# Sheet1.net
KiCad netlist of a schematic drawn in Altium Designer
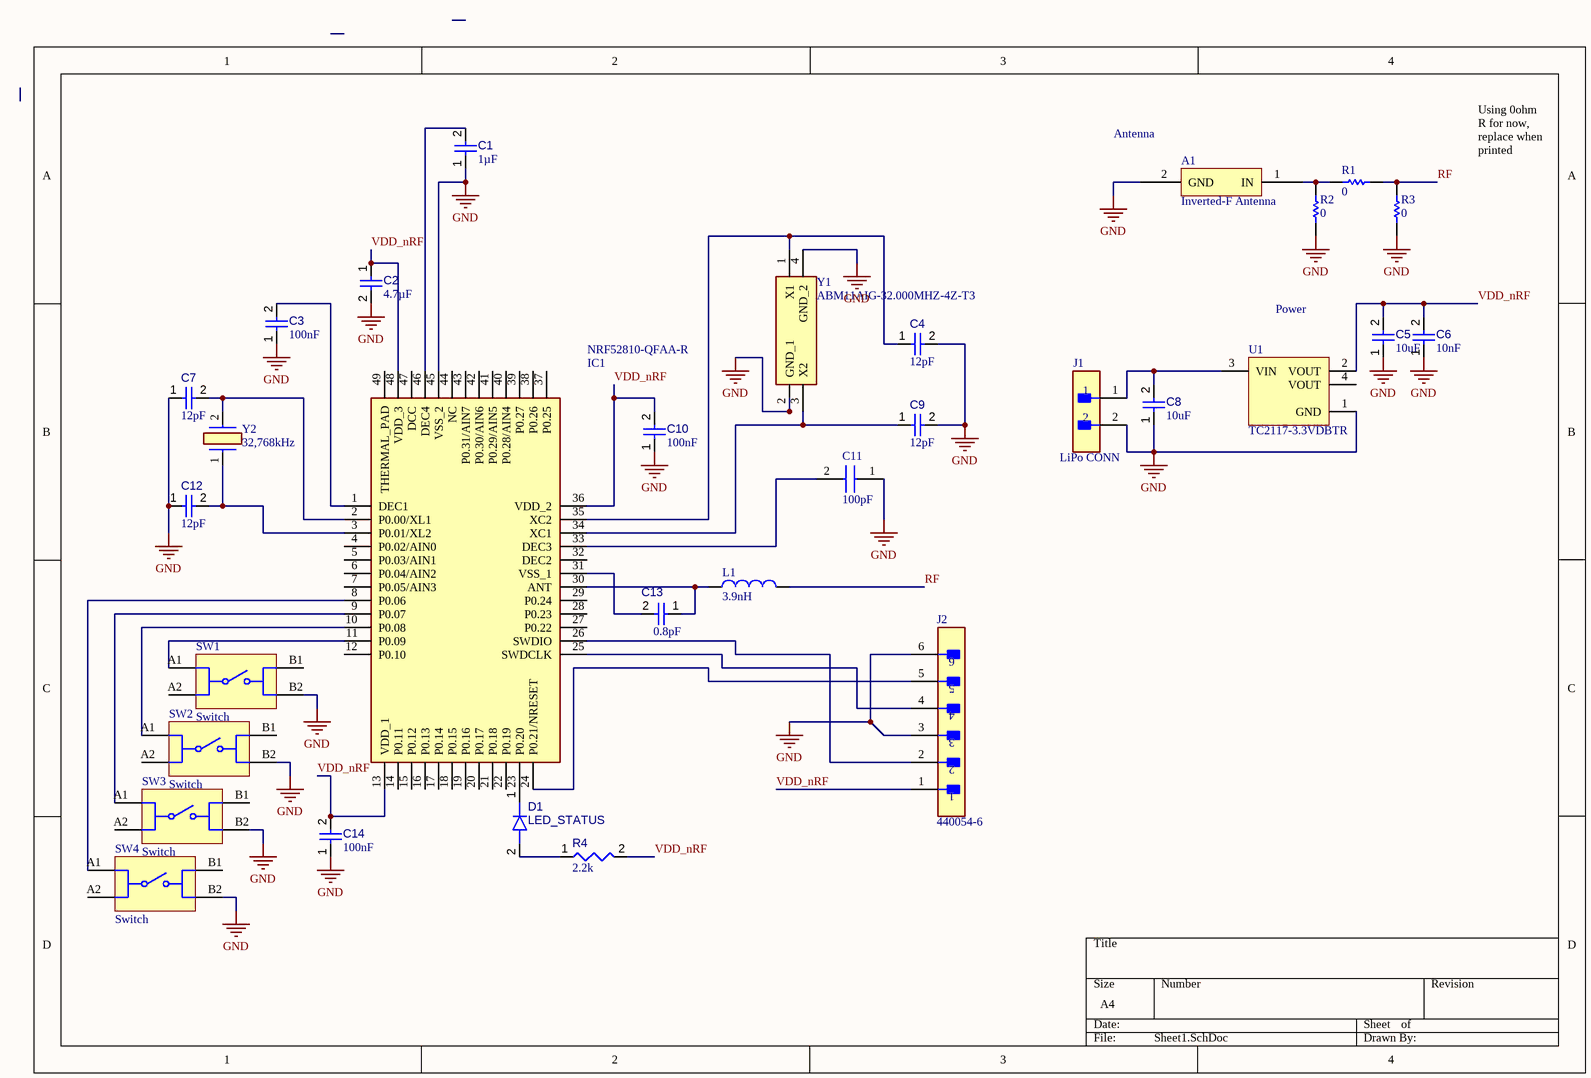
[diagram p0: Sheet1.SchDoc]

(export (version "E")
  (design (tool "Eeschema 10.0.6"))
  (components
    (comp (ref "A1")
      (value "Inverted-F Antenna")
      (footprint "New footprint 1")
      (description "FR4 material 2.48GHz Inverted-F antenna")
      (libsource (lib "Taaseen Basheer") (part "New symbol 1"))
    )
    (comp (ref "C1")
      (value "1µF")
      (footprint "CAPC0603(1608)100_L")
      (description "Chip Capacitor, 1µF +/-0.1%, 25V, 0603, Thickness 1 mm")
      (fields (field (name "TOLERANCE") "20%") (field (name "Comment") "Capacitor 1µF +/-0.1% 25V 0603"))
      (libsource (lib "Taaseen Basheer") (part "CAP-NP-2"))
    )
    (comp (ref "C2")
      (value "4.7µF")
      (footprint "CAPC0603(1608)100_L")
      (description "Chip Capacitor, 4.7µF +/-20%, 10V, 0603, Thickness 1 mm")
      (fields (field (name "TOLERANCE") "10%") (field (name "Comment") "Capacitor 4.7µF +/-20% 10V 0603"))
      (libsource (lib "Taaseen Basheer") (part "CAP-NP-2"))
    )
    (comp (ref "C3")
      (value "100nF")
      (footprint "CAPC1608X90X40NL10T20")
      (description "Chip Capacitor, 100 nF, +/- 10%, 50 V, 0603 (1608 Metric)")
      (fields (field (name "TOLERANCE") "10%") (field (name "Comment") "Capacitor 100 nF +/-10% 50 V 0603"))
      (libsource (lib "Taaseen Basheer") (part "CAP-NP-2"))
    )
    (comp (ref "C4")
      (value "12pF")
      (footprint "CAPC0402(1005)33_L")
      (description "Chip Capacitor, 12pF +/-10%, 50V, 0402, Thickness 0.33 mm")
      (fields (field (name "TOLERANCE") "20%") (field (name "Comment") "Capacitor 12pF +/-10% 50V 0402"))
      (libsource (lib "Taaseen Basheer") (part "CAP-NP-2"))
    )
    (comp (ref "C5")
      (value "10uF")
      (footprint "CAPC0402(1005)33_L")
      (description "Chip Capacitor, 12pF +/-10%, 50V, 0402, Thickness 0.33 mm")
      (fields (field (name "TOLERANCE") "20%") (field (name "Comment") "Capacitor 12pF +/-10% 50V 0402"))
      (libsource (lib "Taaseen Basheer") (part "CAP-NP-2"))
    )
    (comp (ref "C6")
      (value "10nF")
      (footprint "CAPC0402(1005)33_L")
      (description "Chip Capacitor, 12pF +/-10%, 50V, 0402, Thickness 0.33 mm")
      (fields (field (name "TOLERANCE") "20%") (field (name "Comment") "Capacitor 12pF +/-10% 50V 0402"))
      (libsource (lib "Taaseen Basheer") (part "CAP-NP-2"))
    )
    (comp (ref "C7")
      (value "12pF")
      (footprint "CAPC0402(1005)33_L")
      (description "Chip Capacitor, 12pF +/-10%, 50V, 0402, Thickness 0.33 mm")
      (fields (field (name "TOLERANCE") "20%") (field (name "Comment") "Capacitor 12pF +/-10% 50V 0402"))
      (libsource (lib "Taaseen Basheer") (part "CAP-NP-2"))
    )
    (comp (ref "C8")
      (value "10uF")
      (footprint "CAPC0402(1005)33_L")
      (description "Chip Capacitor, 12pF +/-10%, 50V, 0402, Thickness 0.33 mm")
      (fields (field (name "TOLERANCE") "20%") (field (name "Comment") "Capacitor 12pF +/-10% 50V 0402"))
      (libsource (lib "Taaseen Basheer") (part "CAP-NP-2"))
    )
    (comp (ref "C9")
      (value "12pF")
      (footprint "CAPC0402(1005)33_L")
      (description "Chip Capacitor, 12pF +/-10%, 50V, 0402, Thickness 0.33 mm")
      (fields (field (name "TOLERANCE") "20%") (field (name "Comment") "Capacitor 12pF +/-10% 50V 0402"))
      (libsource (lib "Taaseen Basheer") (part "CAP-NP-2"))
    )
    (comp (ref "C10")
      (value "100nF")
      (footprint "CAPC1608X90X40NL10T20")
      (description "Chip Capacitor, 100 nF, +/- 10%, 50 V, 0603 (1608 Metric)")
      (fields (field (name "TOLERANCE") "10%") (field (name "Comment") "Capacitor 100 nF +/-10% 50 V 0603"))
      (libsource (lib "Taaseen Basheer") (part "CAP-NP-2"))
    )
    (comp (ref "C11")
      (value "100pF")
      (footprint "SamacSys:CAPC2012X135N")
      (description "Capacitor")
      (fields
        (field (name "MANUFACTURER_PART_NUMBER") "CL21C101JC61PNC")
        (field (name "MOUSER PART NUMBER") "187-CL21C101JC61PNC")
      )
      (libsource (lib "*") (part "CL21C101JC61PNC"))
    )
    (comp (ref "C12")
      (value "12pF")
      (footprint "CAPC0402(1005)33_L")
      (description "Chip Capacitor, 12pF +/-10%, 50V, 0402, Thickness 0.33 mm")
      (fields (field (name "TOLERANCE") "20%") (field (name "Comment") "Capacitor 12pF +/-10% 50V 0402"))
      (libsource (lib "Taaseen Basheer") (part "CAP-NP-2"))
    )
    (comp (ref "C13")
      (value "0.8pF")
      (footprint "CAPC1005X06N")
      (description "0402 0.8 pF 25 V ±0.5 pF Tolerance SMT Thin-Film RF/Microwave Capacitor")
      (fields (field (name "Comment") "04023J0R8ABSTR"))
      (libsource (lib "Taaseen Basheer") (part "CAP-NP-2"))
    )
    (comp (ref "C14")
      (value "100nF")
      (footprint "CAPC1608X90X40NL10T20")
      (description "Chip Capacitor, 100 nF, +/- 10%, 50 V, 0603 (1608 Metric)")
      (fields (field (name "TOLERANCE") "10%") (field (name "Comment") "Capacitor 100 nF +/-10% 50 V 0603"))
      (libsource (lib "Taaseen Basheer") (part "CAP-NP-2"))
    )
    (comp (ref "D1")
      (value "LED_STATUS")
      (footprint "CAPCP1508X06N")
      (description "1.6 X 0.8 MM SMD CHIP LED LAMP Single Color LED, Green, Water Clear, 0.7mm")
      (libsource (lib "Taaseen Basheer") (part "DIODE-2"))
    )
    (comp (ref "IC1")
      (value "NRF52810-QFAA-R")
      (footprint "SamacSys:QFN40P600X600X90-49N-D")
      (description "Integrated Circuit")
      (fields (field (name "MOUSER PART NUMBER") "949-NRF52810-QFAA-R"))
      (libsource (lib "*") (part "NRF52810-QFAA-R"))
    )
    (comp (ref "J1")
      (value "LiPo CONN")
      (footprint "FP-440054-2-MFG")
      (description "CONN HEADER VERT 2POS 2MM")
      (fields
        (field (name "MANUFACTURER") "TE Connectivity")
        (field (name "MANUFACTURER PART NUMBER") "440054-2")
      )
      (libsource (lib "Altium Content Vault") (part "3bc925449376181038e59eaffc5286c"))
    )
    (comp (ref "J2")
      (value "440054-6")
      (footprint "FP-440054-6-MFG")
      (description "Pin Header, Wire-to-Board, 2 mm, 1 Rows, 6 Contacts, Through Hole Straight, HPI Series")
      (libsource (lib "Taaseen Basheer") (part "f2cb566baf1c37ab5a3b8e90bbeafd6"))
    )
    (comp (ref "L1")
      (value "3.9nH")
      (footprint "CAPC1005X06N")
      (description "General Purpose Inductor, 0.0039uH, 5%, 1 Element, Ceramic-Core, SMD, 0402")
      (fields (field (name "TOLERANCE") "5%") (field (name "Comment") "0402R-3N9J"))
      (libsource (lib "Taaseen Basheer") (part "IND-2"))
    )
    (comp (ref "R1")
      (value "0")
      (footprint "RESC1005X40X25ML05T10")
      (description "Chip Resistor, 0 Ohm, 0.063 W, -55 to 155 degC, 0402 (1005 Metric)")
      (fields (field (name "POWER") "63mW") (field (name "Comment") "Resistor 0R 0402 63 mW"))
      (libsource (lib "Taaseen Basheer") (part "RES-2"))
    )
    (comp (ref "R2")
      (value "0")
      (footprint "RESC1005X40X25ML05T10")
      (description "Chip Resistor, 0 Ohm, 0.063 W, -55 to 155 degC, 0402 (1005 Metric)")
      (fields (field (name "POWER") "63mW") (field (name "Comment") "Resistor 0R 0402 63 mW"))
      (libsource (lib "Taaseen Basheer") (part "RES-2"))
    )
    (comp (ref "R3")
      (value "0")
      (footprint "RESC1005X40X25ML05T10")
      (description "Chip Resistor, 0 Ohm, 0.063 W, -55 to 155 degC, 0402 (1005 Metric)")
      (fields (field (name "POWER") "63mW") (field (name "Comment") "Resistor 0R 0402 63 mW"))
      (libsource (lib "Taaseen Basheer") (part "RES-2"))
    )
    (comp (ref "R4")
      (value "2.2k")
      (footprint "RESC0402(1005)_L")
      (description "Chip Resistor, 2,2 kOhms, +/-5 %, 63 mW, -55 to 155 degC, 0402")
      (fields (field (name "POWER") "63mW") (field (name "TOLERANCE") "5%"))
      (libsource (lib "") (part "RES-2_1"))
    )
    (comp (ref "SW1")
      (value "Switch")
      (footprint "430471035826")
      (description "Tactile Switch, 0.05A, 12Vdc, 260Gf, Smd Rohs Compliant: Yes")
      (libsource (lib "Taaseen Basheer") (part "SPST-NO_4P"))
    )
    (comp (ref "SW2")
      (value "Switch")
      (footprint "430471035826")
      (description "Tactile Switch, 0.05A, 12Vdc, 260Gf, Smd Rohs Compliant: Yes")
      (libsource (lib "Taaseen Basheer") (part "SPST-NO_4P"))
    )
    (comp (ref "SW3")
      (value "Switch")
      (footprint "430471035826")
      (description "Tactile Switch, 0.05A, 12Vdc, 260Gf, Smd Rohs Compliant: Yes")
      (libsource (lib "Taaseen Basheer") (part "SPST-NO_4P"))
    )
    (comp (ref "SW4")
      (value "Switch")
      (footprint "430471035826")
      (description "Tactile Switch, 0.05A, 12Vdc, 260Gf, Smd Rohs Compliant: Yes")
      (libsource (lib "Taaseen Basheer") (part "SPST-NO_4P"))
    )
    (comp (ref "U1")
      (value "TC2117-3.3VDBTR")
      (footprint "SOT-223-DB3_N")
      (description "800 mA Fixed Low Dropout Positive Regulator, 3-Pin SOT-223, Extended Temperature, Tape and Reel")
      (libsource (lib "Altium Content Vault") (part "PM-LINEREG-TC2117-IL4"))
    )
    (comp (ref "Y1")
      (value "ABM11AIG-32.000MHZ-4Z-T3")
      (footprint "SamacSys:ABM11AIG16000MHZ81ZT")
      (description "Crystal or Oscillator")
      (fields (field (name "MOUSER PART NUMBER") "815-M11AIG-32-4ZT3"))
      (libsource (lib "*") (part "ABM11AIG-32.000MHZ-4Z-T3"))
    )
    (comp (ref "Y2")
      (value "32,768kHz")
      (footprint "SamacSys:1TJH125DR1A0058")
      (description "Crystal or Oscillator")
      (fields (field (name "MANUFACTURER_PART_NUMBER") "1TJH125DR1A0058"))
      (libsource (lib "*") (part "1TJH125DR1A0058"))
    )
  )
  (nets
    (net (code "1") (name "/RF") (class "Default")
      (node (ref "L1") (pin "2") (pinfunction "2_2") (pintype "passive"))
      (node (ref "R1") (pin "2") (pinfunction "2_2") (pintype "passive"))
      (node (ref "R3") (pin "2") (pinfunction "2_2") (pintype "passive"))
    )
    (net (code "2") (name "/VDD_nRF") (class "Default")
      (node (ref "C10") (pin "2") (pinfunction "2_2") (pintype "passive"))
      (node (ref "C14") (pin "2") (pinfunction "2_2") (pintype "passive"))
      (node (ref "C2") (pin "1") (pinfunction "1_1") (pintype "passive"))
      (node (ref "C5") (pin "2") (pinfunction "2_2") (pintype "passive"))
      (node (ref "C6") (pin "2") (pinfunction "2_2") (pintype "passive"))
      (node (ref "IC1") (pin "13") (pinfunction "VDD_1_13") (pintype "passive"))
      (node (ref "IC1") (pin "36") (pinfunction "VDD_2_36") (pintype "passive"))
      (node (ref "IC1") (pin "48") (pinfunction "VDD_3_48") (pintype "passive"))
      (node (ref "J2") (pin "1") (pinfunction "1_1") (pintype "passive"))
      (node (ref "R4") (pin "2") (pinfunction "2_2") (pintype "passive"))
      (node (ref "U1") (pin "2") (pinfunction "VOUT_2") (pintype "power_in"))
    )
    (net (code "3") (name "GND") (class "Default")
      (node (ref "A1") (pin "2") (pinfunction "GND_2") (pintype "passive"))
      (node (ref "C1") (pin "1") (pinfunction "1_1") (pintype "passive"))
      (node (ref "C10") (pin "1") (pinfunction "1_1") (pintype "passive"))
      (node (ref "C11") (pin "1") (pinfunction "1_1") (pintype "passive"))
      (node (ref "C12") (pin "1") (pinfunction "1_1") (pintype "passive"))
      (node (ref "C14") (pin "1") (pinfunction "1_1") (pintype "passive"))
      (node (ref "C2") (pin "2") (pinfunction "2_2") (pintype "passive"))
      (node (ref "C3") (pin "1") (pinfunction "1_1") (pintype "passive"))
      (node (ref "C4") (pin "2") (pinfunction "2_2") (pintype "passive"))
      (node (ref "C5") (pin "1") (pinfunction "1_1") (pintype "passive"))
      (node (ref "C6") (pin "1") (pinfunction "1_1") (pintype "passive"))
      (node (ref "C7") (pin "1") (pinfunction "1_1") (pintype "passive"))
      (node (ref "C8") (pin "1") (pinfunction "1_1") (pintype "passive"))
      (node (ref "C9") (pin "2") (pinfunction "2_2") (pintype "passive"))
      (node (ref "IC1") (pin "45") (pinfunction "VSS_2_45") (pintype "passive"))
      (node (ref "J1") (pin "2") (pinfunction "2_2") (pintype "passive"))
      (node (ref "J2") (pin "3") (pinfunction "3_3") (pintype "passive"))
      (node (ref "J2") (pin "6") (pinfunction "6_6") (pintype "passive"))
      (node (ref "R2") (pin "1") (pinfunction "1_1") (pintype "passive"))
      (node (ref "R3") (pin "1") (pinfunction "1_1") (pintype "passive"))
      (node (ref "SW1") (pin "B2") (pinfunction "B2_B2") (pintype "passive"))
      (node (ref "SW2") (pin "B2") (pinfunction "B2_B2") (pintype "passive"))
      (node (ref "SW3") (pin "B2") (pinfunction "B2_B2") (pintype "passive"))
      (node (ref "SW4") (pin "B2") (pinfunction "B2_B2") (pintype "passive"))
      (node (ref "U1") (pin "1") (pinfunction "GND_1") (pintype "power_in"))
      (node (ref "Y1") (pin "2") (pinfunction "GND_1_2") (pintype "passive"))
      (node (ref "Y1") (pin "4") (pinfunction "GND_2_4") (pintype "passive"))
    )
    (net (code "4") (name "Net-(A1-IN)") (class "Default")
      (node (ref "A1") (pin "1") (pinfunction "IN_1") (pintype "passive"))
      (node (ref "R1") (pin "1") (pinfunction "1_1") (pintype "passive"))
      (node (ref "R2") (pin "2") (pinfunction "2_2") (pintype "passive"))
    )
    (net (code "5") (name "Net-(D1-A)") (class "Default")
      (node (ref "D1") (pin "2") (pinfunction "A_2") (pintype "passive"))
      (node (ref "R4") (pin "1") (pinfunction "1_1") (pintype "passive"))
    )
    (net (code "6") (name "Net-(D1-K)") (class "Default")
      (node (ref "D1") (pin "1") (pinfunction "K_1") (pintype "passive"))
      (node (ref "IC1") (pin "23") (pinfunction "P0.20_23") (pintype "passive"))
    )
    (net (code "7") (name "Net-(IC1-ANT)") (class "Default")
      (node (ref "C13") (pin "1") (pinfunction "1_1") (pintype "passive"))
      (node (ref "IC1") (pin "30") (pinfunction "ANT_30") (pintype "passive"))
      (node (ref "L1") (pin "1") (pinfunction "1_1") (pintype "passive"))
    )
    (net (code "8") (name "Net-(IC1-DEC1)") (class "Default")
      (node (ref "C3") (pin "2") (pinfunction "2_2") (pintype "passive"))
      (node (ref "IC1") (pin "1") (pinfunction "DEC1_1") (pintype "passive"))
    )
    (net (code "9") (name "Net-(IC1-DEC3)") (class "Default")
      (node (ref "C11") (pin "2") (pinfunction "2_2") (pintype "passive"))
      (node (ref "IC1") (pin "33") (pinfunction "DEC3_33") (pintype "passive"))
    )
    (net (code "10") (name "Net-(IC1-DEC4)") (class "Default")
      (node (ref "C1") (pin "2") (pinfunction "2_2") (pintype "passive"))
      (node (ref "IC1") (pin "46") (pinfunction "DEC4_46") (pintype "passive"))
    )
    (net (code "11") (name "Net-(IC1-P0.00{slash}XL1)") (class "Default")
      (node (ref "C7") (pin "2") (pinfunction "2_2") (pintype "passive"))
      (node (ref "IC1") (pin "2") (pinfunction "P0.00/XL1_2") (pintype "passive"))
      (node (ref "Y2") (pin "2") (pinfunction "2_2") (pintype "passive"))
    )
    (net (code "12") (name "Net-(IC1-P0.01{slash}XL2)") (class "Default")
      (node (ref "C12") (pin "2") (pinfunction "2_2") (pintype "passive"))
      (node (ref "IC1") (pin "3") (pinfunction "P0.01/XL2_3") (pintype "passive"))
      (node (ref "Y2") (pin "1") (pinfunction "1_1") (pintype "passive"))
    )
    (net (code "13") (name "Net-(IC1-P0.06)") (class "Default")
      (node (ref "IC1") (pin "8") (pinfunction "P0.06_8") (pintype "passive"))
      (node (ref "SW4") (pin "A1") (pinfunction "A1_A1") (pintype "passive"))
    )
    (net (code "14") (name "Net-(IC1-P0.07)") (class "Default")
      (node (ref "IC1") (pin "9") (pinfunction "P0.07_9") (pintype "passive"))
      (node (ref "SW3") (pin "A1") (pinfunction "A1_A1") (pintype "passive"))
    )
    (net (code "15") (name "Net-(IC1-P0.08)") (class "Default")
      (node (ref "IC1") (pin "10") (pinfunction "P0.08_10") (pintype "passive"))
      (node (ref "SW2") (pin "A1") (pinfunction "A1_A1") (pintype "passive"))
    )
    (net (code "16") (name "Net-(IC1-P0.09)") (class "Default")
      (node (ref "IC1") (pin "11") (pinfunction "P0.09_11") (pintype "passive"))
      (node (ref "SW1") (pin "A1") (pinfunction "A1_A1") (pintype "passive"))
    )
    (net (code "17") (name "Net-(IC1-P0.21{slash}NRESET)") (class "Default")
      (node (ref "IC1") (pin "24") (pinfunction "P0.21/NRESET_24") (pintype "passive"))
      (node (ref "J2") (pin "5") (pinfunction "5_5") (pintype "passive"))
    )
    (net (code "18") (name "Net-(IC1-SWDCLK)") (class "Default")
      (node (ref "IC1") (pin "25") (pinfunction "SWDCLK_25") (pintype "passive"))
      (node (ref "J2") (pin "4") (pinfunction "4_4") (pintype "passive"))
    )
    (net (code "19") (name "Net-(IC1-SWDIO)") (class "Default")
      (node (ref "IC1") (pin "26") (pinfunction "SWDIO_26") (pintype "passive"))
      (node (ref "J2") (pin "2") (pinfunction "2_2") (pintype "passive"))
    )
    (net (code "20") (name "Net-(IC1-VSS_1)") (class "Default")
      (node (ref "C13") (pin "2") (pinfunction "2_2") (pintype "passive"))
      (node (ref "IC1") (pin "31") (pinfunction "VSS_1_31") (pintype "passive"))
    )
    (net (code "21") (name "Net-(IC1-XC1)") (class "Default")
      (node (ref "C9") (pin "1") (pinfunction "1_1") (pintype "passive"))
      (node (ref "IC1") (pin "34") (pinfunction "XC1_34") (pintype "passive"))
      (node (ref "Y1") (pin "3") (pinfunction "X2_3") (pintype "passive"))
    )
    (net (code "22") (name "Net-(IC1-XC2)") (class "Default")
      (node (ref "C4") (pin "1") (pinfunction "1_1") (pintype "passive"))
      (node (ref "IC1") (pin "35") (pinfunction "XC2_35") (pintype "passive"))
      (node (ref "Y1") (pin "1") (pinfunction "X1_1") (pintype "passive"))
    )
    (net (code "23") (name "Net-(U1-VIN)") (class "Default")
      (node (ref "C8") (pin "2") (pinfunction "2_2") (pintype "passive"))
      (node (ref "J1") (pin "1") (pinfunction "1_1") (pintype "passive"))
      (node (ref "U1") (pin "3") (pinfunction "VIN_3") (pintype "power_in"))
    )
    (net (code "24") (name "unconnected-(IC1-DCC-Pad47)") (class "Default")
      (node (ref "IC1") (pin "47") (pinfunction "DCC_47") (pintype "passive"))
    )
    (net (code "25") (name "unconnected-(IC1-DEC2-Pad32)") (class "Default")
      (node (ref "IC1") (pin "32") (pinfunction "DEC2_32") (pintype "passive"))
    )
    (net (code "26") (name "unconnected-(IC1-NC-Pad44)") (class "Default")
      (node (ref "IC1") (pin "44") (pinfunction "NC_44") (pintype "passive"))
    )
    (net (code "27") (name "unconnected-(IC1-P0.02{slash}AIN0-Pad4)") (class "Default")
      (node (ref "IC1") (pin "4") (pinfunction "P0.02/AIN0_4") (pintype "passive"))
    )
    (net (code "28") (name "unconnected-(IC1-P0.03{slash}AIN1-Pad5)") (class "Default")
      (node (ref "IC1") (pin "5") (pinfunction "P0.03/AIN1_5") (pintype "passive"))
    )
    (net (code "29") (name "unconnected-(IC1-P0.04{slash}AIN2-Pad6)") (class "Default")
      (node (ref "IC1") (pin "6") (pinfunction "P0.04/AIN2_6") (pintype "passive"))
    )
    (net (code "30") (name "unconnected-(IC1-P0.05{slash}AIN3-Pad7)") (class "Default")
      (node (ref "IC1") (pin "7") (pinfunction "P0.05/AIN3_7") (pintype "passive"))
    )
    (net (code "31") (name "unconnected-(IC1-P0.10-Pad12)") (class "Default")
      (node (ref "IC1") (pin "12") (pinfunction "P0.10_12") (pintype "passive"))
    )
    (net (code "32") (name "unconnected-(IC1-P0.11-Pad14)") (class "Default")
      (node (ref "IC1") (pin "14") (pinfunction "P0.11_14") (pintype "passive"))
    )
    (net (code "33") (name "unconnected-(IC1-P0.12-Pad15)") (class "Default")
      (node (ref "IC1") (pin "15") (pinfunction "P0.12_15") (pintype "passive"))
    )
    (net (code "34") (name "unconnected-(IC1-P0.13-Pad16)") (class "Default")
      (node (ref "IC1") (pin "16") (pinfunction "P0.13_16") (pintype "passive"))
    )
    (net (code "35") (name "unconnected-(IC1-P0.14-Pad17)") (class "Default")
      (node (ref "IC1") (pin "17") (pinfunction "P0.14_17") (pintype "passive"))
    )
    (net (code "36") (name "unconnected-(IC1-P0.15-Pad18)") (class "Default")
      (node (ref "IC1") (pin "18") (pinfunction "P0.15_18") (pintype "passive"))
    )
    (net (code "37") (name "unconnected-(IC1-P0.16-Pad19)") (class "Default")
      (node (ref "IC1") (pin "19") (pinfunction "P0.16_19") (pintype "passive"))
    )
    (net (code "38") (name "unconnected-(IC1-P0.17-Pad20)") (class "Default")
      (node (ref "IC1") (pin "20") (pinfunction "P0.17_20") (pintype "passive"))
    )
    (net (code "39") (name "unconnected-(IC1-P0.18-Pad21)") (class "Default")
      (node (ref "IC1") (pin "21") (pinfunction "P0.18_21") (pintype "passive"))
    )
    (net (code "40") (name "unconnected-(IC1-P0.19-Pad22)") (class "Default")
      (node (ref "IC1") (pin "22") (pinfunction "P0.19_22") (pintype "passive"))
    )
    (net (code "41") (name "unconnected-(IC1-P0.22-Pad27)") (class "Default")
      (node (ref "IC1") (pin "27") (pinfunction "P0.22_27") (pintype "passive"))
    )
    (net (code "42") (name "unconnected-(IC1-P0.23-Pad28)") (class "Default")
      (node (ref "IC1") (pin "28") (pinfunction "P0.23_28") (pintype "passive"))
    )
    (net (code "43") (name "unconnected-(IC1-P0.24-Pad29)") (class "Default")
      (node (ref "IC1") (pin "29") (pinfunction "P0.24_29") (pintype "passive"))
    )
    (net (code "44") (name "unconnected-(IC1-P0.25-Pad37)") (class "Default")
      (node (ref "IC1") (pin "37") (pinfunction "P0.25_37") (pintype "passive"))
    )
    (net (code "45") (name "unconnected-(IC1-P0.26-Pad38)") (class "Default")
      (node (ref "IC1") (pin "38") (pinfunction "P0.26_38") (pintype "passive"))
    )
    (net (code "46") (name "unconnected-(IC1-P0.27-Pad39)") (class "Default")
      (node (ref "IC1") (pin "39") (pinfunction "P0.27_39") (pintype "passive"))
    )
    (net (code "47") (name "unconnected-(IC1-P0.28{slash}AIN4-Pad40)") (class "Default")
      (node (ref "IC1") (pin "40") (pinfunction "P0.28/AIN4_40") (pintype "passive"))
    )
    (net (code "48") (name "unconnected-(IC1-P0.29{slash}AIN5-Pad41)") (class "Default")
      (node (ref "IC1") (pin "41") (pinfunction "P0.29/AIN5_41") (pintype "passive"))
    )
    (net (code "49") (name "unconnected-(IC1-P0.30{slash}AIN6-Pad42)") (class "Default")
      (node (ref "IC1") (pin "42") (pinfunction "P0.30/AIN6_42") (pintype "passive"))
    )
    (net (code "50") (name "unconnected-(IC1-P0.31{slash}AIN7-Pad43)") (class "Default")
      (node (ref "IC1") (pin "43") (pinfunction "P0.31/AIN7_43") (pintype "passive"))
    )
    (net (code "51") (name "unconnected-(IC1-THERMAL_PAD-Pad49)") (class "Default")
      (node (ref "IC1") (pin "49") (pinfunction "THERMAL_PAD_49") (pintype "passive"))
    )
    (net (code "52") (name "unconnected-(SW1-PadA2)") (class "Default")
      (node (ref "SW1") (pin "A2") (pinfunction "A2_A2") (pintype "passive"))
    )
    (net (code "53") (name "unconnected-(SW1-PadB1)") (class "Default")
      (node (ref "SW1") (pin "B1") (pinfunction "B1_B1") (pintype "passive"))
    )
    (net (code "54") (name "unconnected-(SW2-PadA2)") (class "Default")
      (node (ref "SW2") (pin "A2") (pinfunction "A2_A2") (pintype "passive"))
    )
    (net (code "55") (name "unconnected-(SW2-PadB1)") (class "Default")
      (node (ref "SW2") (pin "B1") (pinfunction "B1_B1") (pintype "passive"))
    )
    (net (code "56") (name "unconnected-(SW3-PadA2)") (class "Default")
      (node (ref "SW3") (pin "A2") (pinfunction "A2_A2") (pintype "passive"))
    )
    (net (code "57") (name "unconnected-(SW3-PadB1)") (class "Default")
      (node (ref "SW3") (pin "B1") (pinfunction "B1_B1") (pintype "passive"))
    )
    (net (code "58") (name "unconnected-(SW4-PadA2)") (class "Default")
      (node (ref "SW4") (pin "A2") (pinfunction "A2_A2") (pintype "passive"))
    )
    (net (code "59") (name "unconnected-(SW4-PadB1)") (class "Default")
      (node (ref "SW4") (pin "B1") (pinfunction "B1_B1") (pintype "passive"))
    )
    (net (code "60") (name "unconnected-(U1-VOUT-Pad4)") (class "Default")
      (node (ref "U1") (pin "4") (pinfunction "VOUT_4") (pintype "power_in"))
    )
  )
)
